# DOORLOCK_v5.net
KiCad netlist of a schematic drawn in EAGLE
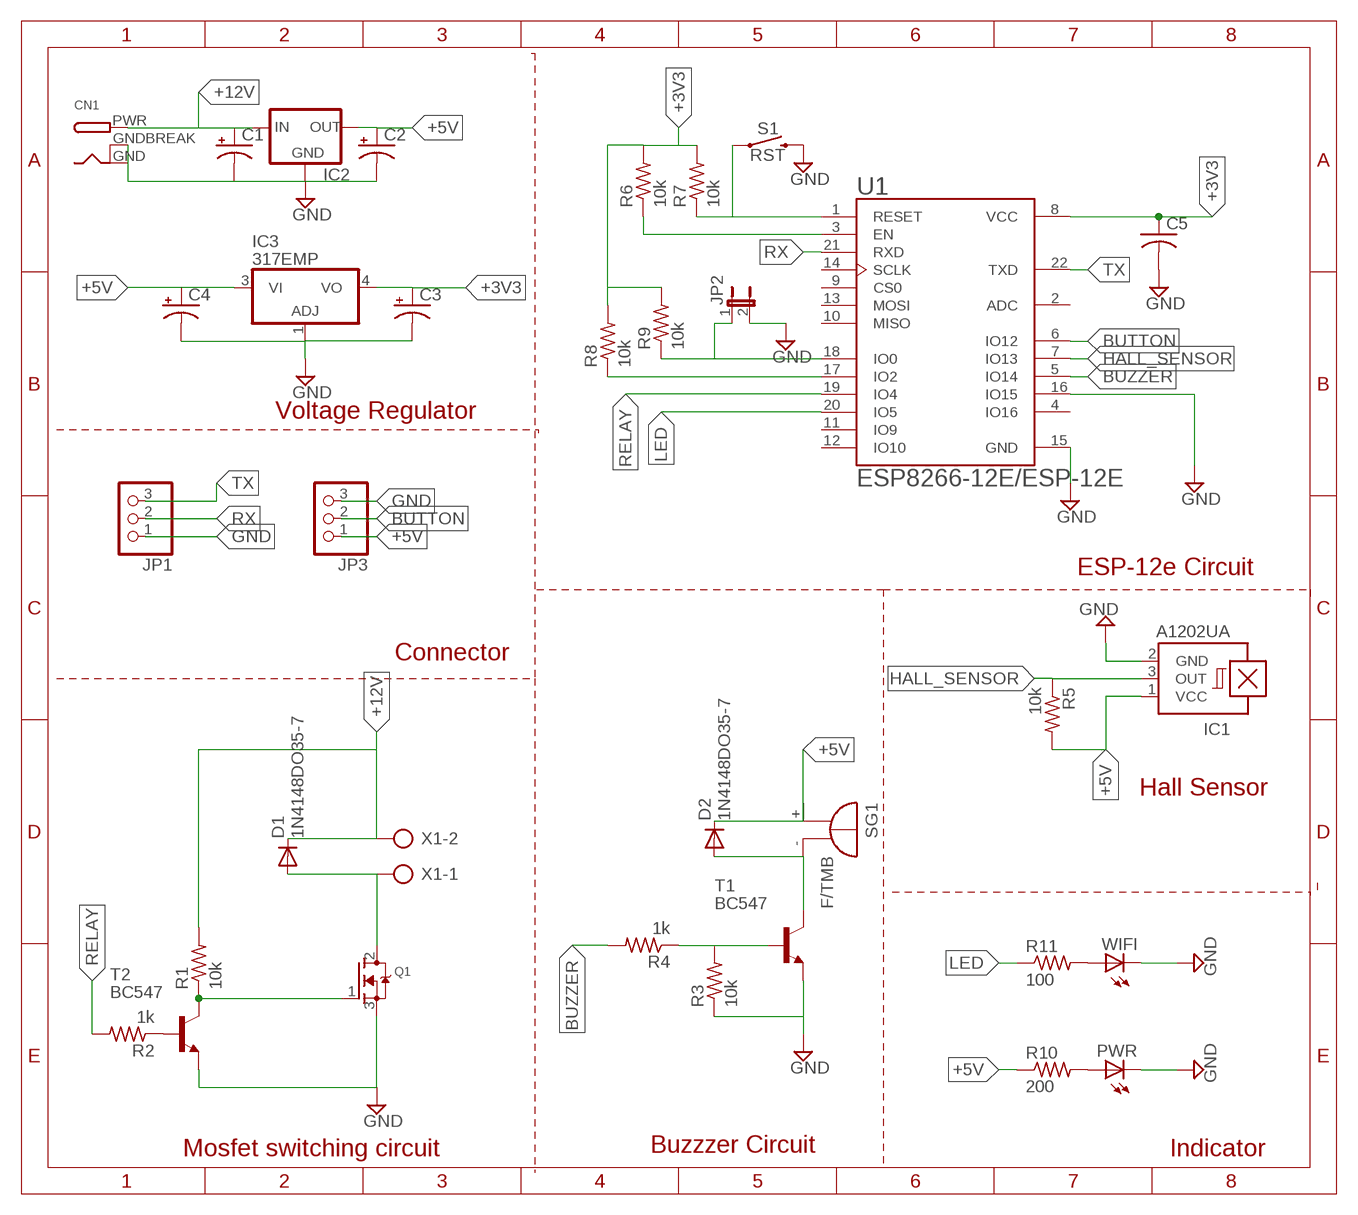
[diagram p0: schematic, sheet 1]

(export (version "E")
  (design (tool "Eeschema 10.0.6"))
  (components
    (comp (ref "C1")
      (value "CPOL-USE2.5-5")
      (footprint "eagle-import:E2,5-5")
      (libsource (lib "eagle-import") (part "CPOL-USE2.5-5"))
    )
    (comp (ref "C2")
      (value "CPOL-USE2.5-5")
      (footprint "eagle-import:E2,5-5")
      (libsource (lib "eagle-import") (part "CPOL-USE2.5-5"))
    )
    (comp (ref "C3")
      (value "CPOL-USE2.5-5")
      (footprint "eagle-import:E2,5-5")
      (libsource (lib "eagle-import") (part "CPOL-USE2.5-5"))
    )
    (comp (ref "C4")
      (value "CPOL-USE2.5-5")
      (footprint "eagle-import:E2,5-5")
      (libsource (lib "eagle-import") (part "CPOL-USE2.5-5"))
    )
    (comp (ref "C5")
      (value "C-US025-030X050")
      (footprint "eagle-import:C025-030X050")
      (libsource (lib "eagle-import") (part "C-US025-030X050"))
    )
    (comp (ref "CN1")
      (value "DCBARRELPTH")
      (footprint "eagle-import:DCJACK_2MM_PTH")
      (libsource (lib "eagle-import") (part "DCBARRELPTH"))
    )
    (comp (ref "D1")
      (value "1N4148DO35-7")
      (footprint "eagle-import:DO35-7")
      (libsource (lib "eagle-import") (part "1N4148DO35-7"))
    )
    (comp (ref "D2")
      (value "1N4148DO35-7")
      (footprint "eagle-import:DO35-7")
      (libsource (lib "eagle-import") (part "1N4148DO35-7"))
    )
    (comp (ref "IC1")
      (value "A1202UA")
      (footprint "eagle-import:SIP3-UA")
      (libsource (lib "eagle-import") (part "A12?UA02"))
    )
    (comp (ref "IC2")
      (value "78XXS")
      (footprint "eagle-import:78XXS")
      (libsource (lib "eagle-import") (part "78XXS"))
    )
    (comp (ref "IC3")
      (value "317EMP")
      (footprint "eagle-import:SOT223")
      (libsource (lib "eagle-import") (part "317EMP"))
    )
    (comp (ref "JP1")
      (value "PINHD-1X3")
      (footprint "eagle-import:1X03")
      (libsource (lib "eagle-import") (part "PINHD-1X3"))
    )
    (comp (ref "JP2")
      (value "JP1E")
      (footprint "eagle-import:JP1")
      (libsource (lib "eagle-import") (part "JP1E"))
    )
    (comp (ref "JP3")
      (value "PINHD-1X3")
      (footprint "eagle-import:1X03")
      (libsource (lib "eagle-import") (part "PINHD-1X3"))
    )
    (comp (ref "PWR")
      (value "LED3MM")
      (footprint "eagle-import:LED3MM")
      (libsource (lib "eagle-import") (part "LED3MM"))
    )
    (comp (ref "Q1")
      (value "MOSFET-NGDS_TO220V")
      (footprint "eagle-import:TO220V")
      (libsource (lib "eagle-import") (part "MOSFET-NGDS_TO220V"))
    )
    (comp (ref "R1")
      (value "10k")
      (footprint "eagle-import:0207_2V")
      (libsource (lib "eagle-import") (part "R-US_0207/2V"))
    )
    (comp (ref "R2")
      (value "1k")
      (footprint "eagle-import:0207_2V")
      (libsource (lib "eagle-import") (part "R-US_0207/2V"))
    )
    (comp (ref "R3")
      (value "10k")
      (footprint "eagle-import:0207_2V")
      (libsource (lib "eagle-import") (part "R-US_0207/2V"))
    )
    (comp (ref "R4")
      (value "1k")
      (footprint "eagle-import:0207_2V")
      (libsource (lib "eagle-import") (part "R-US_0207/2V"))
    )
    (comp (ref "R5")
      (value "10k")
      (footprint "eagle-import:0207_2V")
      (libsource (lib "eagle-import") (part "R-US_0207/2V"))
    )
    (comp (ref "R6")
      (value "10k")
      (footprint "eagle-import:0207_2V")
      (libsource (lib "eagle-import") (part "R-US_0207/2V"))
    )
    (comp (ref "R7")
      (value "10k")
      (footprint "eagle-import:0207_2V")
      (libsource (lib "eagle-import") (part "R-US_0207/2V"))
    )
    (comp (ref "R8")
      (value "10k")
      (footprint "eagle-import:0207_2V")
      (libsource (lib "eagle-import") (part "R-US_0207/2V"))
    )
    (comp (ref "R9")
      (value "10k")
      (footprint "eagle-import:0207_2V")
      (libsource (lib "eagle-import") (part "R-US_0207/2V"))
    )
    (comp (ref "R10")
      (value "200")
      (footprint "eagle-import:0207_2V")
      (libsource (lib "eagle-import") (part "R-US_0207/2V"))
    )
    (comp (ref "R11")
      (value "100")
      (footprint "eagle-import:0207_2V")
      (libsource (lib "eagle-import") (part "R-US_0207/2V"))
    )
    (comp (ref "S1")
      (value "RST")
      (footprint "eagle-import:TACTILE_SWITCH_PTH_6.0MM")
      (libsource (lib "eagle-import") (part "MOMENTARY-SWITCH-SPST-PTH-6.0MM"))
    )
    (comp (ref "SG1")
      (value "F/TMB")
      (footprint "eagle-import:F_TMB")
      (libsource (lib "eagle-import") (part "F/TMB"))
    )
    (comp (ref "T1")
      (value "BC547")
      (footprint "eagle-import:TO92")
      (libsource (lib "eagle-import") (part "BC547"))
    )
    (comp (ref "T2")
      (value "BC547")
      (footprint "eagle-import:TO92")
      (libsource (lib "eagle-import") (part "BC547"))
    )
    (comp (ref "U1")
      (value "ESP8266-12E/ESP-12E")
      (footprint "eagle-import:XCVR_ESP8266-12E_ESP-12E")
      (fields (field (name "MF") "AI-Thinker"))
      (libsource (lib "eagle-import") (part "ESP8266-12E/ESP-12E"))
    )
    (comp (ref "WIFI")
      (value "LED3MM")
      (footprint "eagle-import:LED3MM")
      (libsource (lib "eagle-import") (part "LED3MM"))
    )
    (comp (ref "X1")
      (value "AK500/2-H")
      (footprint "eagle-import:AK500_2-H")
      (libsource (lib "eagle-import") (part "AK500/2-H"))
    )
  )
  (nets
    (net (code "1") (name "+3V3") (class "Default")
      (node (ref "C3") (pin "+") (pinfunction "+_+") (pintype "passive"))
      (node (ref "C5") (pin "1") (pinfunction "1_1") (pintype "passive"))
      (node (ref "IC3") (pin "4") (pinfunction "VO_4") (pintype "passive"))
      (node (ref "R6") (pin "2") (pinfunction "2_2") (pintype "passive"))
      (node (ref "R7") (pin "2") (pinfunction "2_2") (pintype "passive"))
      (node (ref "R8") (pin "2") (pinfunction "2_2") (pintype "passive"))
      (node (ref "R9") (pin "2") (pinfunction "2_2") (pintype "passive"))
      (node (ref "U1") (pin "8") (pinfunction "VCC_8") (pintype "power_in"))
    )
    (net (code "2") (name "+5V") (class "Default")
      (node (ref "C2") (pin "+") (pinfunction "+_+") (pintype "passive"))
      (node (ref "C4") (pin "+") (pinfunction "+_+") (pintype "passive"))
      (node (ref "D2") (pin "C") (pinfunction "C_C") (pintype "passive"))
      (node (ref "IC1") (pin "1") (pinfunction "VCC_1") (pintype "power_in"))
      (node (ref "IC2") (pin "OUT") (pinfunction "OUT_OUT") (pintype "passive"))
      (node (ref "IC3") (pin "3") (pinfunction "VI_3") (pintype "input"))
      (node (ref "JP3") (pin "1") (pinfunction "1_1") (pintype "passive"))
      (node (ref "R10") (pin "1") (pinfunction "1_1") (pintype "passive"))
      (node (ref "R5") (pin "2") (pinfunction "2_2") (pintype "passive"))
      (node (ref "SG1") (pin "+") (pinfunction "+_+") (pintype "passive"))
    )
    (net (code "3") (name "+12V") (class "Default")
      (node (ref "C1") (pin "+") (pinfunction "+_+") (pintype "passive"))
      (node (ref "CN1") (pin "PWR") (pinfunction "PWR_PWR") (pintype "power_in"))
      (node (ref "D1") (pin "C") (pinfunction "C_C") (pintype "passive"))
      (node (ref "IC2") (pin "IN") (pinfunction "IN_IN") (pintype "input"))
      (node (ref "R1") (pin "2") (pinfunction "2_2") (pintype "passive"))
      (node (ref "X1") (pin "2") (pinfunction "KL_2") (pintype "passive"))
    )
    (net (code "4") (name "BUTTON") (class "Default")
      (node (ref "JP3") (pin "2") (pinfunction "2_2") (pintype "passive"))
      (node (ref "U1") (pin "6") (pinfunction "IO12_6") (pintype "bidirectional"))
    )
    (net (code "5") (name "BUZZER") (class "Default")
      (node (ref "R4") (pin "2") (pinfunction "2_2") (pintype "passive"))
      (node (ref "U1") (pin "5") (pinfunction "IO14_5") (pintype "bidirectional"))
    )
    (net (code "6") (name "GND") (class "Default")
      (node (ref "C1") (pin "-") (pinfunction "-_-") (pintype "passive"))
      (node (ref "C2") (pin "-") (pinfunction "-_-") (pintype "passive"))
      (node (ref "C3") (pin "-") (pinfunction "-_-") (pintype "passive"))
      (node (ref "C4") (pin "-") (pinfunction "-_-") (pintype "passive"))
      (node (ref "C5") (pin "2") (pinfunction "2_2") (pintype "passive"))
      (node (ref "CN1") (pin "GND") (pinfunction "GND_GND") (pintype "power_in"))
      (node (ref "CN1") (pin "GNDBREAK") (pinfunction "GNDBREAK_GNDBREAK") (pintype "power_in"))
      (node (ref "IC1") (pin "2") (pinfunction "GND_2") (pintype "power_in"))
      (node (ref "IC2") (pin "GND") (pinfunction "GND_GND") (pintype "input"))
      (node (ref "IC3") (pin "1") (pinfunction "ADJ_1") (pintype "input"))
      (node (ref "JP1") (pin "1") (pinfunction "1_1") (pintype "passive"))
      (node (ref "JP2") (pin "2") (pinfunction "2_2") (pintype "passive"))
      (node (ref "JP3") (pin "3") (pinfunction "3_3") (pintype "passive"))
      (node (ref "PWR") (pin "K") (pinfunction "C_K") (pintype "passive"))
      (node (ref "Q1") (pin "3") (pinfunction "S_3") (pintype "bidirectional"))
      (node (ref "R3") (pin "1") (pinfunction "1_1") (pintype "passive"))
      (node (ref "S1") (pin "3") (pinfunction "2_3") (pintype "passive"))
      (node (ref "T1") (pin "1") (pinfunction "E_1") (pintype "passive"))
      (node (ref "T2") (pin "1") (pinfunction "E_1") (pintype "passive"))
      (node (ref "U1") (pin "15") (pinfunction "GND_15") (pintype "power_in"))
      (node (ref "U1") (pin "16") (pinfunction "IO15_16") (pintype "bidirectional"))
      (node (ref "WIFI") (pin "K") (pinfunction "C_K") (pintype "passive"))
    )
    (net (code "7") (name "HALL_SENSOR") (class "Default")
      (node (ref "IC1") (pin "3") (pinfunction "OUT_3") (pintype "output"))
      (node (ref "R5") (pin "1") (pinfunction "1_1") (pintype "passive"))
      (node (ref "U1") (pin "7") (pinfunction "IO13_7") (pintype "bidirectional"))
    )
    (net (code "8") (name "LED") (class "Default")
      (node (ref "R11") (pin "1") (pinfunction "1_1") (pintype "passive"))
      (node (ref "U1") (pin "20") (pinfunction "IO5_20") (pintype "bidirectional"))
    )
    (net (code "9") (name "Net-(PWR-PadA)") (class "Default")
      (node (ref "PWR") (pin "A") (pinfunction "A_A") (pintype "passive"))
      (node (ref "R10") (pin "2") (pinfunction "2_2") (pintype "passive"))
    )
    (net (code "10") (name "Net-(Q1-D)") (class "Default")
      (node (ref "D1") (pin "A") (pinfunction "A_A") (pintype "passive"))
      (node (ref "Q1") (pin "2") (pinfunction "D_2") (pintype "bidirectional"))
      (node (ref "X1") (pin "1") (pinfunction "KL_1") (pintype "passive"))
    )
    (net (code "11") (name "Net-(Q1-G)") (class "Default")
      (node (ref "Q1") (pin "1") (pinfunction "G_1") (pintype "bidirectional"))
      (node (ref "R1") (pin "1") (pinfunction "1_1") (pintype "passive"))
      (node (ref "T2") (pin "3") (pinfunction "C_3") (pintype "passive"))
    )
    (net (code "12") (name "Net-(R11-Pad2)") (class "Default")
      (node (ref "R11") (pin "2") (pinfunction "2_2") (pintype "passive"))
      (node (ref "WIFI") (pin "A") (pinfunction "A_A") (pintype "passive"))
    )
    (net (code "13") (name "Net-(T1-B)") (class "Default")
      (node (ref "R3") (pin "2") (pinfunction "2_2") (pintype "passive"))
      (node (ref "R4") (pin "1") (pinfunction "1_1") (pintype "passive"))
      (node (ref "T1") (pin "2") (pinfunction "B_2") (pintype "passive"))
    )
    (net (code "14") (name "Net-(T1-C)") (class "Default")
      (node (ref "D2") (pin "A") (pinfunction "A_A") (pintype "passive"))
      (node (ref "SG1") (pin "-") (pinfunction "-_-") (pintype "passive"))
      (node (ref "T1") (pin "3") (pinfunction "C_3") (pintype "passive"))
    )
    (net (code "15") (name "Net-(T2-B)") (class "Default")
      (node (ref "R2") (pin "1") (pinfunction "1_1") (pintype "passive"))
      (node (ref "T2") (pin "2") (pinfunction "B_2") (pintype "passive"))
    )
    (net (code "16") (name "Net-(U1-EN)") (class "Default")
      (node (ref "R6") (pin "1") (pinfunction "1_1") (pintype "passive"))
      (node (ref "U1") (pin "3") (pinfunction "EN_3") (pintype "input"))
    )
    (net (code "17") (name "Net-(U1-IO0)") (class "Default")
      (node (ref "JP2") (pin "1") (pinfunction "1_1") (pintype "passive"))
      (node (ref "R9") (pin "1") (pinfunction "1_1") (pintype "passive"))
      (node (ref "U1") (pin "18") (pinfunction "IO0_18") (pintype "bidirectional"))
    )
    (net (code "18") (name "Net-(U1-IO2)") (class "Default")
      (node (ref "R8") (pin "1") (pinfunction "1_1") (pintype "passive"))
      (node (ref "U1") (pin "17") (pinfunction "IO2_17") (pintype "bidirectional"))
    )
    (net (code "19") (name "Net-(U1-RESET)") (class "Default")
      (node (ref "R7") (pin "1") (pinfunction "1_1") (pintype "passive"))
      (node (ref "S1") (pin "1") (pinfunction "1_1") (pintype "passive"))
      (node (ref "U1") (pin "1") (pinfunction "RESET_1") (pintype "input"))
    )
    (net (code "20") (name "RELAY") (class "Default")
      (node (ref "R2") (pin "2") (pinfunction "2_2") (pintype "passive"))
      (node (ref "U1") (pin "19") (pinfunction "IO4_19") (pintype "bidirectional"))
    )
    (net (code "21") (name "RX") (class "Default")
      (node (ref "JP1") (pin "2") (pinfunction "2_2") (pintype "passive"))
      (node (ref "U1") (pin "21") (pinfunction "RXD_21") (pintype "input"))
    )
    (net (code "22") (name "TX") (class "Default")
      (node (ref "JP1") (pin "3") (pinfunction "3_3") (pintype "passive"))
      (node (ref "U1") (pin "22") (pinfunction "TXD_22") (pintype "output"))
    )
    (net (code "23") (name "unconnected-(U1-ADC-Pad2)") (class "Default")
      (node (ref "U1") (pin "2") (pinfunction "ADC_2") (pintype "passive"))
    )
    (net (code "24") (name "unconnected-(U1-CS0-Pad9)") (class "Default")
      (node (ref "U1") (pin "9") (pinfunction "CS0_9") (pintype "input"))
    )
    (net (code "25") (name "unconnected-(U1-IO9-Pad11)") (class "Default")
      (node (ref "U1") (pin "11") (pinfunction "IO9_11") (pintype "bidirectional"))
    )
    (net (code "26") (name "unconnected-(U1-IO10-Pad12)") (class "Default")
      (node (ref "U1") (pin "12") (pinfunction "IO10_12") (pintype "bidirectional"))
    )
    (net (code "27") (name "unconnected-(U1-IO16-Pad4)") (class "Default")
      (node (ref "U1") (pin "4") (pinfunction "IO16_4") (pintype "bidirectional"))
    )
    (net (code "28") (name "unconnected-(U1-MISO-Pad10)") (class "Default")
      (node (ref "U1") (pin "10") (pinfunction "MISO_10") (pintype "bidirectional"))
    )
    (net (code "29") (name "unconnected-(U1-MOSI-Pad13)") (class "Default")
      (node (ref "U1") (pin "13") (pinfunction "MOSI_13") (pintype "bidirectional"))
    )
    (net (code "30") (name "unconnected-(U1-SCLK-Pad14)") (class "Default")
      (node (ref "U1") (pin "14") (pinfunction "SCLK_14") (pintype "input"))
    )
  )
)
